# UI_Board_TOP.net
KiCad netlist of a schematic drawn in Altium Designer
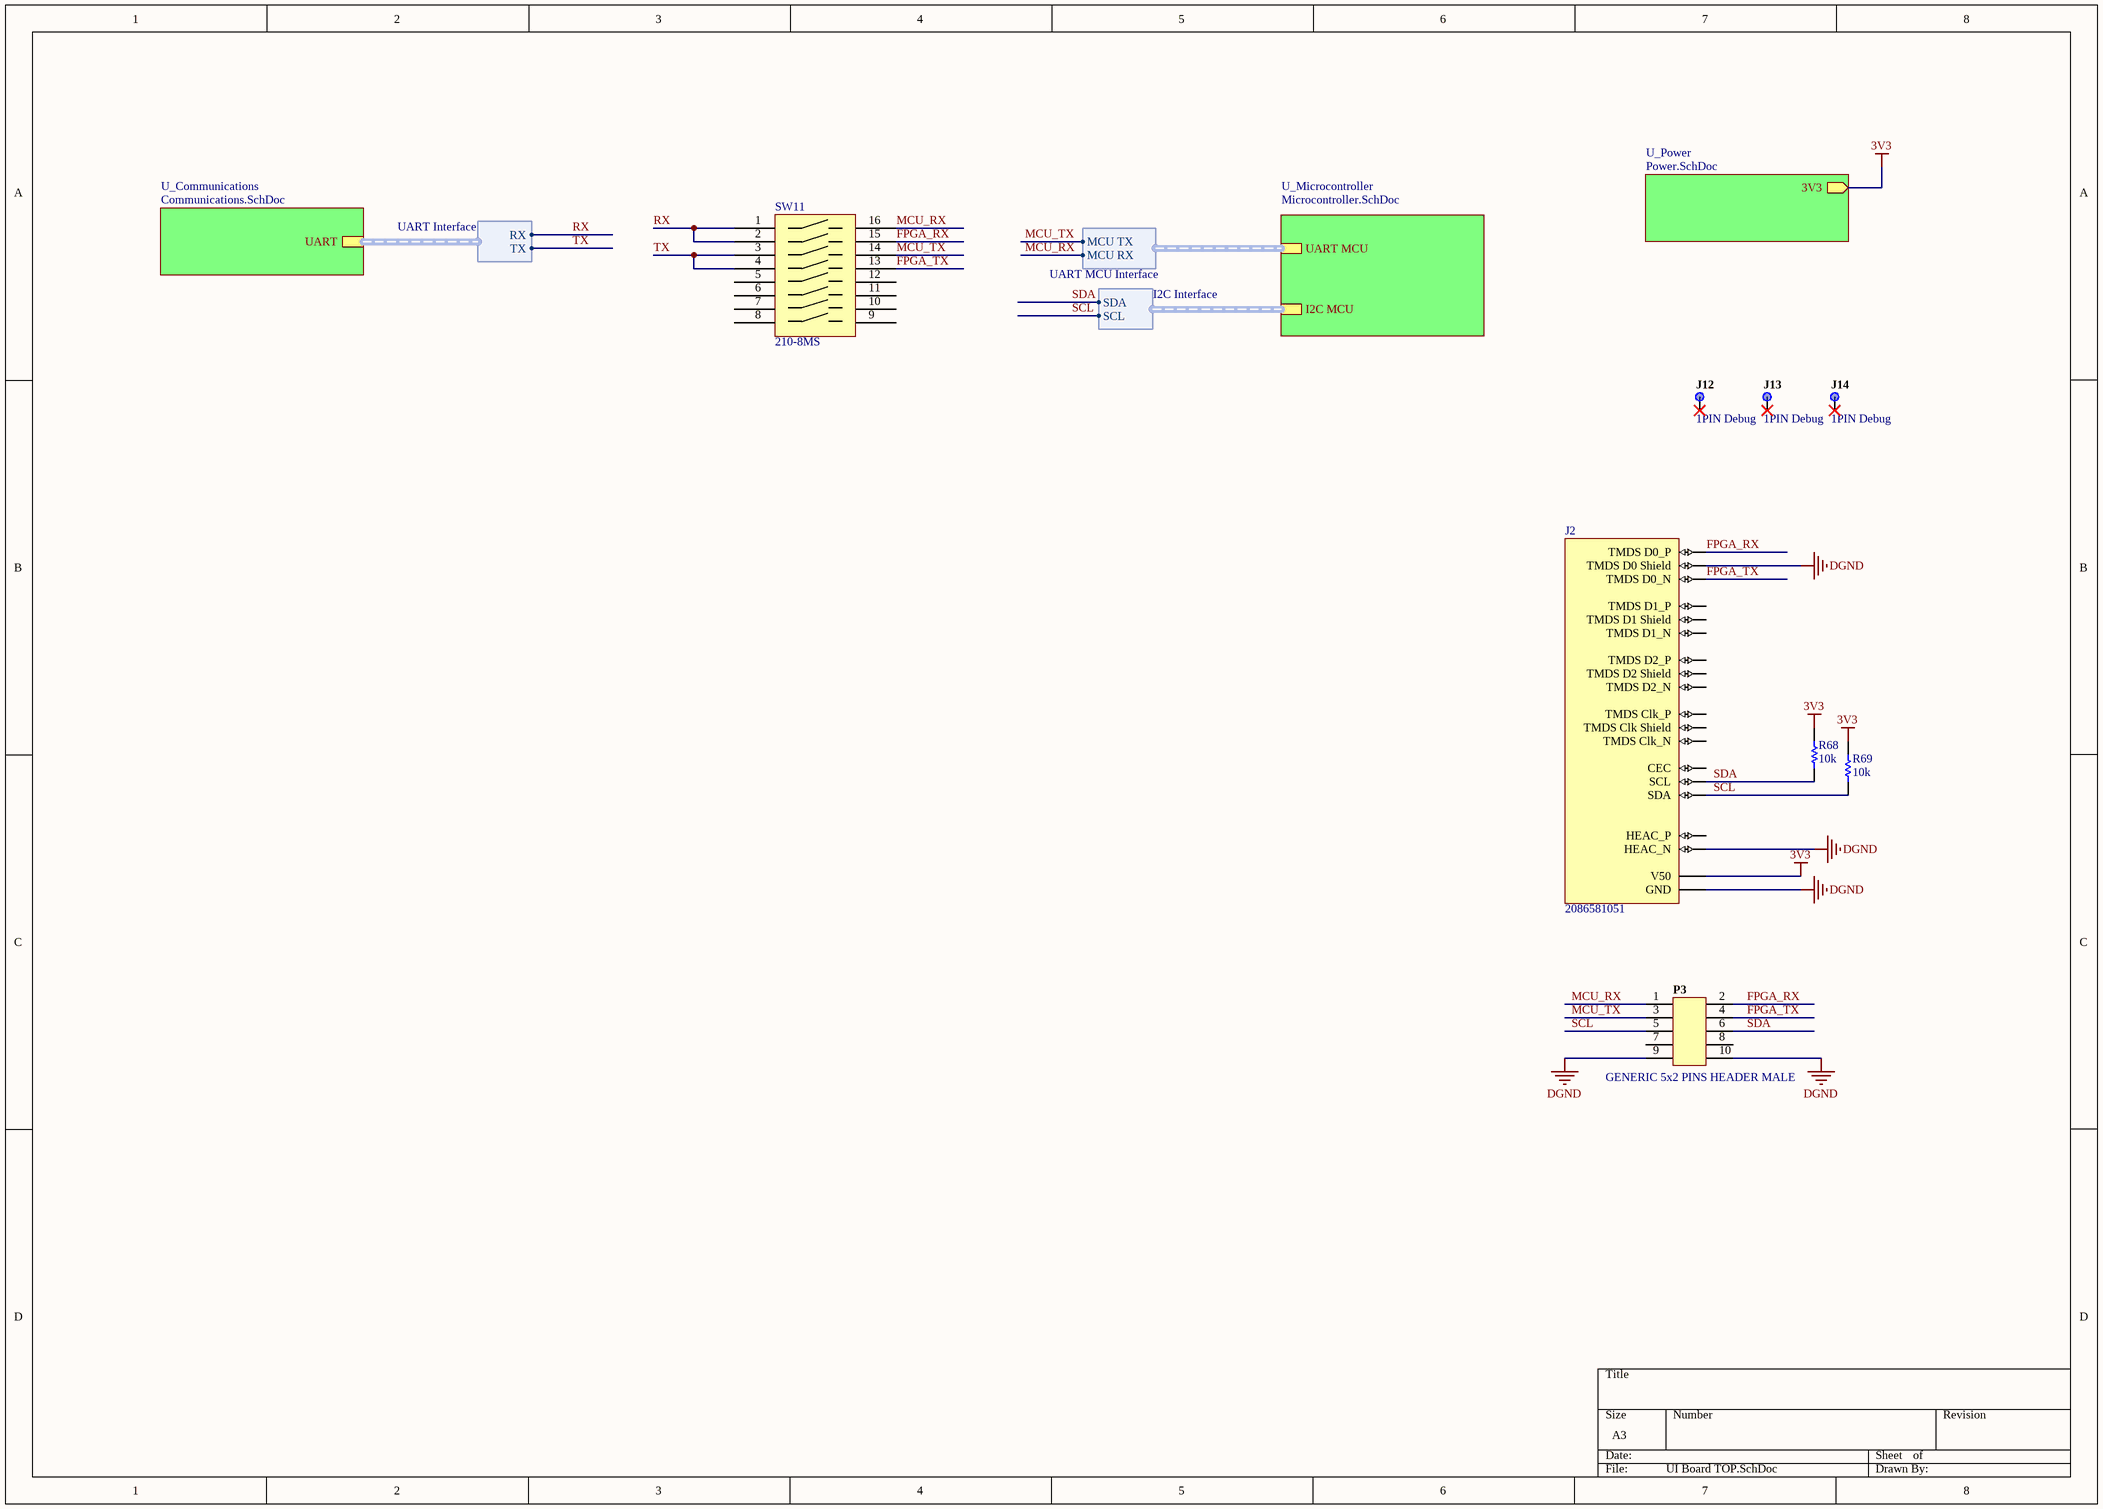
[diagram p0: UI Board TOP.SchDoc]

(export (version "E")
  (design (tool "Eeschema 10.0.6"))
  (components
    (comp (ref "J2")
      (value "2086581051")
      (footprint "2086581051")
      (description "CONN FEM SMD 19 90Deg HDMI")
      (fields (field (name "DESIGN ITEM ID") "2086581051") (field (name "MANUFACTURER") "Molex"))
      (libsource (lib "University of Malta - MEMENTO") (part "Symbol"))
    )
    (comp (ref "J12")
      (value "1PIN Debug")
      (footprint "1 Pin Debug Port 0.9mm")
      (description "CONN MAL TH 1 0Deg HEADER")
      (fields (field (name "DESIGN ITEM ID") "1PIN Debug"))
      (libsource (lib "University of Malta - MEMENTO") (part "1PIN Debug"))
    )
    (comp (ref "J13")
      (value "1PIN Debug")
      (footprint "1 Pin Debug Port 0.9mm")
      (description "CONN MAL TH 1 0Deg HEADER")
      (fields (field (name "DESIGN ITEM ID") "1PIN Debug"))
      (libsource (lib "University of Malta - MEMENTO") (part "1PIN Debug"))
    )
    (comp (ref "J14")
      (value "1PIN Debug")
      (footprint "1 Pin Debug Port 0.9mm")
      (description "CONN MAL TH 1 0Deg HEADER")
      (fields (field (name "DESIGN ITEM ID") "1PIN Debug"))
      (libsource (lib "University of Malta - MEMENTO") (part "1PIN Debug"))
    )
    (comp (ref "P3")
      (value "GENERIC 5x2 PINS HEADER MALE")
      (footprint "GENERIC 5PIN 2ROW HEADER 0")
      (description "CONN MAL TH 5x2 0Deg HEADER")
      (fields
        (field (name "DESIGN ITEM ID") "GENERIC 5x2 PINS HEADER MALE")
        (field (name "MANUFACTURER") "Generic")
      )
      (libsource (lib "University of Malta - MEMENTO") (part "GENERIC 5x2 PINS HEADER MALE"))
    )
    (comp (ref "R68")
      (value "10k")
      (footprint "0402-M")
      (description "RES-10k-0402-63mW-5%")
      (fields (field (name "MANUFACTURER") "Generic") (field (name "Comment") "RES 10k 0402 63mW 5%"))
      (libsource (lib "") (part "Symbol_1"))
    )
    (comp (ref "R69")
      (value "10k")
      (footprint "0402-M")
      (description "RES-10k-0402-63mW-5%")
      (fields (field (name "MANUFACTURER") "Generic") (field (name "Comment") "RES 10k 0402 63mW 5%"))
      (libsource (lib "") (part "Symbol_1"))
    )
    (comp (ref "SW11")
      (value "210-8MS")
      (footprint "210-8MS")
      (description "SWITCH DIP SMD SPST 8 100mA 50V")
      (fields (field (name "MANUFACTURER") "C&K Components") (field (name "DESIGN ITEM ID") "210-8MS"))
      (libsource (lib "University of Malta - MEMENTO") (part "210-8MS"))
    )
  )
  (nets
    (net (code "5") (name "/FPGA_RX") (class "Default")
      (node (ref "J2") (pin "7") (pinfunction "TMDS_D0_P_7") (pintype "bidirectional"))
      (node (ref "P3") (pin "2") (pinfunction "2_2") (pintype "passive"))
      (node (ref "SW11") (pin "15") (pinfunction "SW2.in_15") (pintype "passive"))
    )
    (net (code "6") (name "/FPGA_TX") (class "Default")
      (node (ref "J2") (pin "9") (pinfunction "TMDS_D0_N_9") (pintype "bidirectional"))
      (node (ref "P3") (pin "4") (pinfunction "4_4") (pintype "passive"))
      (node (ref "SW11") (pin "13") (pinfunction "SW4.in_13") (pintype "passive"))
    )
    (net (code "7") (name "/MCU_RX") (class "Default")
      (node (ref "P3") (pin "1") (pinfunction "1_1") (pintype "passive"))
      (node (ref "SW11") (pin "16") (pinfunction "SW1_16") (pintype "passive"))
    )
    (net (code "8") (name "/MCU_TX") (class "Default")
      (node (ref "P3") (pin "3") (pinfunction "3_3") (pintype "passive"))
      (node (ref "SW11") (pin "14") (pinfunction "SW3.in_14") (pintype "passive"))
    )
    (net (code "9") (name "/RX") (class "Default")
      (node (ref "SW11") (pin "1") (pinfunction "SW1_1") (pintype "passive"))
      (node (ref "SW11") (pin "2") (pinfunction "SW2_2") (pintype "passive"))
    )
    (net (code "10") (name "/SCL") (class "Default")
      (node (ref "J2") (pin "16") (pinfunction "SDA_16") (pintype "bidirectional"))
      (node (ref "P3") (pin "5") (pinfunction "5_5") (pintype "passive"))
      (node (ref "R69") (pin "1") (pinfunction "1_1") (pintype "passive"))
    )
    (net (code "11") (name "/SDA") (class "Default")
      (node (ref "J2") (pin "15") (pinfunction "SCL_15") (pintype "bidirectional"))
      (node (ref "P3") (pin "6") (pinfunction "6_6") (pintype "passive"))
      (node (ref "R68") (pin "1") (pinfunction "1_1") (pintype "passive"))
    )
    (net (code "12") (name "/TX") (class "Default")
      (node (ref "SW11") (pin "3") (pinfunction "SW3_3") (pintype "passive"))
      (node (ref "SW11") (pin "4") (pinfunction "SW4_4") (pintype "passive"))
    )
    (net (code "16") (name "3V3") (class "Default")
      (node (ref "J2") (pin "18") (pinfunction "V50_18") (pintype "power_in"))
      (node (ref "R68") (pin "2") (pinfunction "2_2") (pintype "passive"))
      (node (ref "R69") (pin "2") (pinfunction "2_2") (pintype "passive"))
    )
    (net (code "17") (name "DGND") (class "Default")
      (node (ref "J2") (pin "17") (pinfunction "GND_17") (pintype "power_in"))
      (node (ref "J2") (pin "19") (pinfunction "HEAC_N_19") (pintype "bidirectional"))
      (node (ref "J2") (pin "8") (pinfunction "TMDS_D0_Shield_8") (pintype "bidirectional"))
      (node (ref "P3") (pin "10") (pinfunction "10_10") (pintype "passive"))
      (node (ref "P3") (pin "9") (pinfunction "9_9") (pintype "passive"))
    )
    (net (code "18") (name "unconnected-(J2-CEC-Pad13)") (class "Default")
      (node (ref "J2") (pin "13") (pinfunction "CEC_13") (pintype "bidirectional"))
    )
    (net (code "19") (name "unconnected-(J2-HEAC_P-Pad14)") (class "Default")
      (node (ref "J2") (pin "14") (pinfunction "HEAC_P_14") (pintype "bidirectional"))
    )
    (net (code "20") (name "unconnected-(J2-TMDS_Clk_N-Pad12)") (class "Default")
      (node (ref "J2") (pin "12") (pinfunction "TMDS_Clk_N_12") (pintype "bidirectional"))
    )
    (net (code "21") (name "unconnected-(J2-TMDS_Clk_P-Pad10)") (class "Default")
      (node (ref "J2") (pin "10") (pinfunction "TMDS_Clk_P_10") (pintype "bidirectional"))
    )
    (net (code "22") (name "unconnected-(J2-TMDS_Clk_Shield-Pad11)") (class "Default")
      (node (ref "J2") (pin "11") (pinfunction "TMDS_Clk_Shield_11") (pintype "bidirectional"))
    )
    (net (code "23") (name "unconnected-(J2-TMDS_D1_N-Pad6)") (class "Default")
      (node (ref "J2") (pin "6") (pinfunction "TMDS_D1_N_6") (pintype "bidirectional"))
    )
    (net (code "24") (name "unconnected-(J2-TMDS_D1_P-Pad4)") (class "Default")
      (node (ref "J2") (pin "4") (pinfunction "TMDS_D1_P_4") (pintype "bidirectional"))
    )
    (net (code "25") (name "unconnected-(J2-TMDS_D1_Shield-Pad5)") (class "Default")
      (node (ref "J2") (pin "5") (pinfunction "TMDS_D1_Shield_5") (pintype "bidirectional"))
    )
    (net (code "26") (name "unconnected-(J2-TMDS_D2_N-Pad3)") (class "Default")
      (node (ref "J2") (pin "3") (pinfunction "TMDS_D2_N_3") (pintype "bidirectional"))
    )
    (net (code "27") (name "unconnected-(J2-TMDS_D2_P-Pad1)") (class "Default")
      (node (ref "J2") (pin "1") (pinfunction "TMDS_D2_P_1") (pintype "bidirectional"))
    )
    (net (code "28") (name "unconnected-(J2-TMDS_D2_Shield-Pad2)") (class "Default")
      (node (ref "J2") (pin "2") (pinfunction "TMDS_D2_Shield_2") (pintype "bidirectional"))
    )
    (net (code "29") (name "unconnected-(J12-Pad1)") (class "Default")
      (node (ref "J12") (pin "1") (pinfunction "1_1") (pintype "passive+no_connect"))
    )
    (net (code "30") (name "unconnected-(J13-Pad1)") (class "Default")
      (node (ref "J13") (pin "1") (pinfunction "1_1") (pintype "passive+no_connect"))
    )
    (net (code "31") (name "unconnected-(J14-Pad1)") (class "Default")
      (node (ref "J14") (pin "1") (pinfunction "1_1") (pintype "passive+no_connect"))
    )
    (net (code "32") (name "unconnected-(P3-Pad7)") (class "Default")
      (node (ref "P3") (pin "7") (pinfunction "7_7") (pintype "passive"))
    )
    (net (code "33") (name "unconnected-(P3-Pad8)") (class "Default")
      (node (ref "P3") (pin "8") (pinfunction "8_8") (pintype "passive"))
    )
    (net (code "34") (name "unconnected-(SW11-Pad7)") (class "Default")
      (node (ref "SW11") (pin "7") (pinfunction "7_7") (pintype "passive"))
    )
    (net (code "35") (name "unconnected-(SW11-SW1-Pad5)") (class "Default")
      (node (ref "SW11") (pin "5") (pinfunction "SW1_5") (pintype "passive"))
    )
    (net (code "36") (name "unconnected-(SW11-SW1.in-Pad12)") (class "Default")
      (node (ref "SW11") (pin "12") (pinfunction "SW1.in_12") (pintype "passive"))
    )
    (net (code "37") (name "unconnected-(SW11-SW2-Pad6)") (class "Default")
      (node (ref "SW11") (pin "6") (pinfunction "SW2_6") (pintype "passive"))
    )
    (net (code "38") (name "unconnected-(SW11-SW2.in-Pad11)") (class "Default")
      (node (ref "SW11") (pin "11") (pinfunction "SW2.in_11") (pintype "passive"))
    )
    (net (code "39") (name "unconnected-(SW11-SW3.in-Pad10)") (class "Default")
      (node (ref "SW11") (pin "10") (pinfunction "SW3.in_10") (pintype "passive"))
    )
    (net (code "40") (name "unconnected-(SW11-SW4-Pad8)") (class "Default")
      (node (ref "SW11") (pin "8") (pinfunction "SW4_8") (pintype "passive"))
    )
    (net (code "41") (name "unconnected-(SW11-SW4.in-Pad9)") (class "Default")
      (node (ref "SW11") (pin "9") (pinfunction "SW4.in_9") (pintype "passive"))
    )
  )
)
